# servoyolu.net
KiCad netlist of a schematic drawn in EAGLE
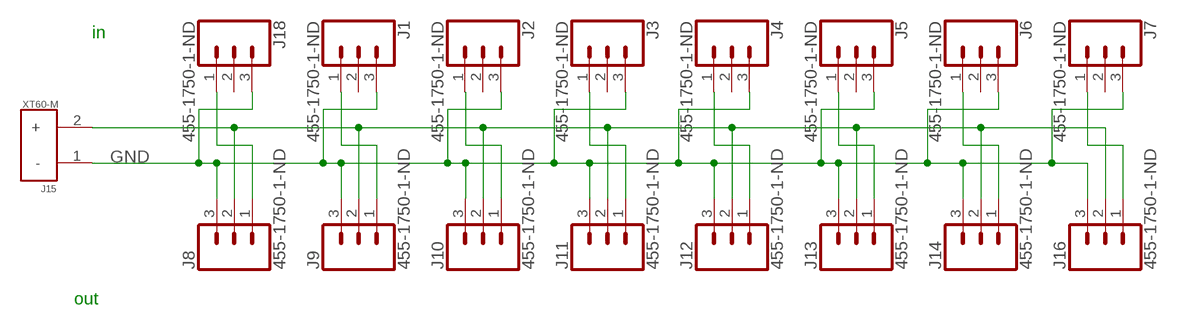
[diagram p0: schematic, sheet 1]

(export (version "E")
  (design (tool "Eeschema 10.0.6"))
  (components
    (comp (ref "J1")
      (value "455-1750-1-ND")
      (footprint "eagle-import:1X03")
      (libsource (lib "eagle-import") (part "CONN_03"))
    )
    (comp (ref "J2")
      (value "455-1750-1-ND")
      (footprint "eagle-import:1X03")
      (libsource (lib "eagle-import") (part "CONN_03"))
    )
    (comp (ref "J3")
      (value "455-1750-1-ND")
      (footprint "eagle-import:1X03")
      (libsource (lib "eagle-import") (part "CONN_03"))
    )
    (comp (ref "J4")
      (value "455-1750-1-ND")
      (footprint "eagle-import:1X03")
      (libsource (lib "eagle-import") (part "CONN_03"))
    )
    (comp (ref "J5")
      (value "455-1750-1-ND")
      (footprint "eagle-import:1X03")
      (libsource (lib "eagle-import") (part "CONN_03"))
    )
    (comp (ref "J6")
      (value "455-1750-1-ND")
      (footprint "eagle-import:1X03")
      (libsource (lib "eagle-import") (part "CONN_03"))
    )
    (comp (ref "J7")
      (value "455-1750-1-ND")
      (footprint "eagle-import:1X03")
      (libsource (lib "eagle-import") (part "CONN_03"))
    )
    (comp (ref "J8")
      (value "455-1750-1-ND")
      (footprint "eagle-import:1X03")
      (libsource (lib "eagle-import") (part "CONN_03"))
    )
    (comp (ref "J9")
      (value "455-1750-1-ND")
      (footprint "eagle-import:1X03")
      (libsource (lib "eagle-import") (part "CONN_03"))
    )
    (comp (ref "J10")
      (value "455-1750-1-ND")
      (footprint "eagle-import:1X03")
      (libsource (lib "eagle-import") (part "CONN_03"))
    )
    (comp (ref "J11")
      (value "455-1750-1-ND")
      (footprint "eagle-import:1X03")
      (libsource (lib "eagle-import") (part "CONN_03"))
    )
    (comp (ref "J12")
      (value "455-1750-1-ND")
      (footprint "eagle-import:1X03")
      (libsource (lib "eagle-import") (part "CONN_03"))
    )
    (comp (ref "J13")
      (value "455-1750-1-ND")
      (footprint "eagle-import:1X03")
      (libsource (lib "eagle-import") (part "CONN_03"))
    )
    (comp (ref "J14")
      (value "455-1750-1-ND")
      (footprint "eagle-import:1X03")
      (libsource (lib "eagle-import") (part "CONN_03"))
    )
    (comp (ref "J15")
      (value "XT60-M")
      (footprint "eagle-import:AMASS_XT60-M")
      (fields (field (name "MF") "AMASS"))
      (libsource (lib "eagle-import") (part "XT60-M"))
    )
    (comp (ref "J16")
      (value "455-1750-1-ND")
      (footprint "eagle-import:1X03")
      (libsource (lib "eagle-import") (part "CONN_03"))
    )
    (comp (ref "J18")
      (value "455-1750-1-ND")
      (footprint "eagle-import:1X03")
      (libsource (lib "eagle-import") (part "CONN_03"))
    )
  )
  (nets
    (net (code "1") (name "/GND") (class "Default")
      (node (ref "J1") (pin "3") (pinfunction "3_3") (pintype "passive"))
      (node (ref "J10") (pin "3") (pinfunction "3_3") (pintype "passive"))
      (node (ref "J11") (pin "3") (pinfunction "3_3") (pintype "passive"))
      (node (ref "J12") (pin "3") (pinfunction "3_3") (pintype "passive"))
      (node (ref "J13") (pin "3") (pinfunction "3_3") (pintype "passive"))
      (node (ref "J14") (pin "3") (pinfunction "3_3") (pintype "passive"))
      (node (ref "J15") (pin "1") (pinfunction "-_1") (pintype "passive"))
      (node (ref "J16") (pin "3") (pinfunction "3_3") (pintype "passive"))
      (node (ref "J18") (pin "3") (pinfunction "3_3") (pintype "passive"))
      (node (ref "J2") (pin "3") (pinfunction "3_3") (pintype "passive"))
      (node (ref "J3") (pin "3") (pinfunction "3_3") (pintype "passive"))
      (node (ref "J4") (pin "3") (pinfunction "3_3") (pintype "passive"))
      (node (ref "J5") (pin "3") (pinfunction "3_3") (pintype "passive"))
      (node (ref "J6") (pin "3") (pinfunction "3_3") (pintype "passive"))
      (node (ref "J7") (pin "3") (pinfunction "3_3") (pintype "passive"))
      (node (ref "J8") (pin "3") (pinfunction "3_3") (pintype "passive"))
      (node (ref "J9") (pin "3") (pinfunction "3_3") (pintype "passive"))
    )
    (net (code "2") (name "Net-(J1-Pad1)") (class "Default")
      (node (ref "J1") (pin "1") (pinfunction "1_1") (pintype "passive"))
      (node (ref "J9") (pin "1") (pinfunction "1_1") (pintype "passive"))
    )
    (net (code "3") (name "Net-(J10-Pad1)") (class "Default")
      (node (ref "J10") (pin "1") (pinfunction "1_1") (pintype "passive"))
      (node (ref "J2") (pin "1") (pinfunction "1_1") (pintype "passive"))
    )
    (net (code "4") (name "Net-(J11-Pad1)") (class "Default")
      (node (ref "J11") (pin "1") (pinfunction "1_1") (pintype "passive"))
      (node (ref "J3") (pin "1") (pinfunction "1_1") (pintype "passive"))
    )
    (net (code "5") (name "Net-(J12-Pad1)") (class "Default")
      (node (ref "J12") (pin "1") (pinfunction "1_1") (pintype "passive"))
      (node (ref "J4") (pin "1") (pinfunction "1_1") (pintype "passive"))
    )
    (net (code "6") (name "Net-(J13-Pad1)") (class "Default")
      (node (ref "J13") (pin "1") (pinfunction "1_1") (pintype "passive"))
      (node (ref "J5") (pin "1") (pinfunction "1_1") (pintype "passive"))
    )
    (net (code "7") (name "Net-(J14-Pad1)") (class "Default")
      (node (ref "J14") (pin "1") (pinfunction "1_1") (pintype "passive"))
      (node (ref "J6") (pin "1") (pinfunction "1_1") (pintype "passive"))
    )
    (net (code "8") (name "Net-(J15-+)") (class "Default")
      (node (ref "J10") (pin "2") (pinfunction "2_2") (pintype "passive"))
      (node (ref "J11") (pin "2") (pinfunction "2_2") (pintype "passive"))
      (node (ref "J12") (pin "2") (pinfunction "2_2") (pintype "passive"))
      (node (ref "J13") (pin "2") (pinfunction "2_2") (pintype "passive"))
      (node (ref "J14") (pin "2") (pinfunction "2_2") (pintype "passive"))
      (node (ref "J15") (pin "2") (pinfunction "+_2") (pintype "passive"))
      (node (ref "J16") (pin "2") (pinfunction "2_2") (pintype "passive"))
      (node (ref "J8") (pin "2") (pinfunction "2_2") (pintype "passive"))
      (node (ref "J9") (pin "2") (pinfunction "2_2") (pintype "passive"))
    )
    (net (code "9") (name "Net-(J16-Pad1)") (class "Default")
      (node (ref "J16") (pin "1") (pinfunction "1_1") (pintype "passive"))
      (node (ref "J7") (pin "1") (pinfunction "1_1") (pintype "passive"))
    )
    (net (code "10") (name "Net-(J18-Pad1)") (class "Default")
      (node (ref "J18") (pin "1") (pinfunction "1_1") (pintype "passive"))
      (node (ref "J8") (pin "1") (pinfunction "1_1") (pintype "passive"))
    )
    (net (code "11") (name "unconnected-(J1-Pad2)") (class "Default")
      (node (ref "J1") (pin "2") (pinfunction "2_2") (pintype "passive"))
    )
    (net (code "12") (name "unconnected-(J2-Pad2)") (class "Default")
      (node (ref "J2") (pin "2") (pinfunction "2_2") (pintype "passive"))
    )
    (net (code "13") (name "unconnected-(J3-Pad2)") (class "Default")
      (node (ref "J3") (pin "2") (pinfunction "2_2") (pintype "passive"))
    )
    (net (code "14") (name "unconnected-(J4-Pad2)") (class "Default")
      (node (ref "J4") (pin "2") (pinfunction "2_2") (pintype "passive"))
    )
    (net (code "15") (name "unconnected-(J5-Pad2)") (class "Default")
      (node (ref "J5") (pin "2") (pinfunction "2_2") (pintype "passive"))
    )
    (net (code "16") (name "unconnected-(J6-Pad2)") (class "Default")
      (node (ref "J6") (pin "2") (pinfunction "2_2") (pintype "passive"))
    )
    (net (code "17") (name "unconnected-(J7-Pad2)") (class "Default")
      (node (ref "J7") (pin "2") (pinfunction "2_2") (pintype "passive"))
    )
    (net (code "18") (name "unconnected-(J18-Pad2)") (class "Default")
      (node (ref "J18") (pin "2") (pinfunction "2_2") (pintype "passive"))
    )
  )
)
